# S7_RF.net
KiCad netlist of a schematic drawn in Altium Designer
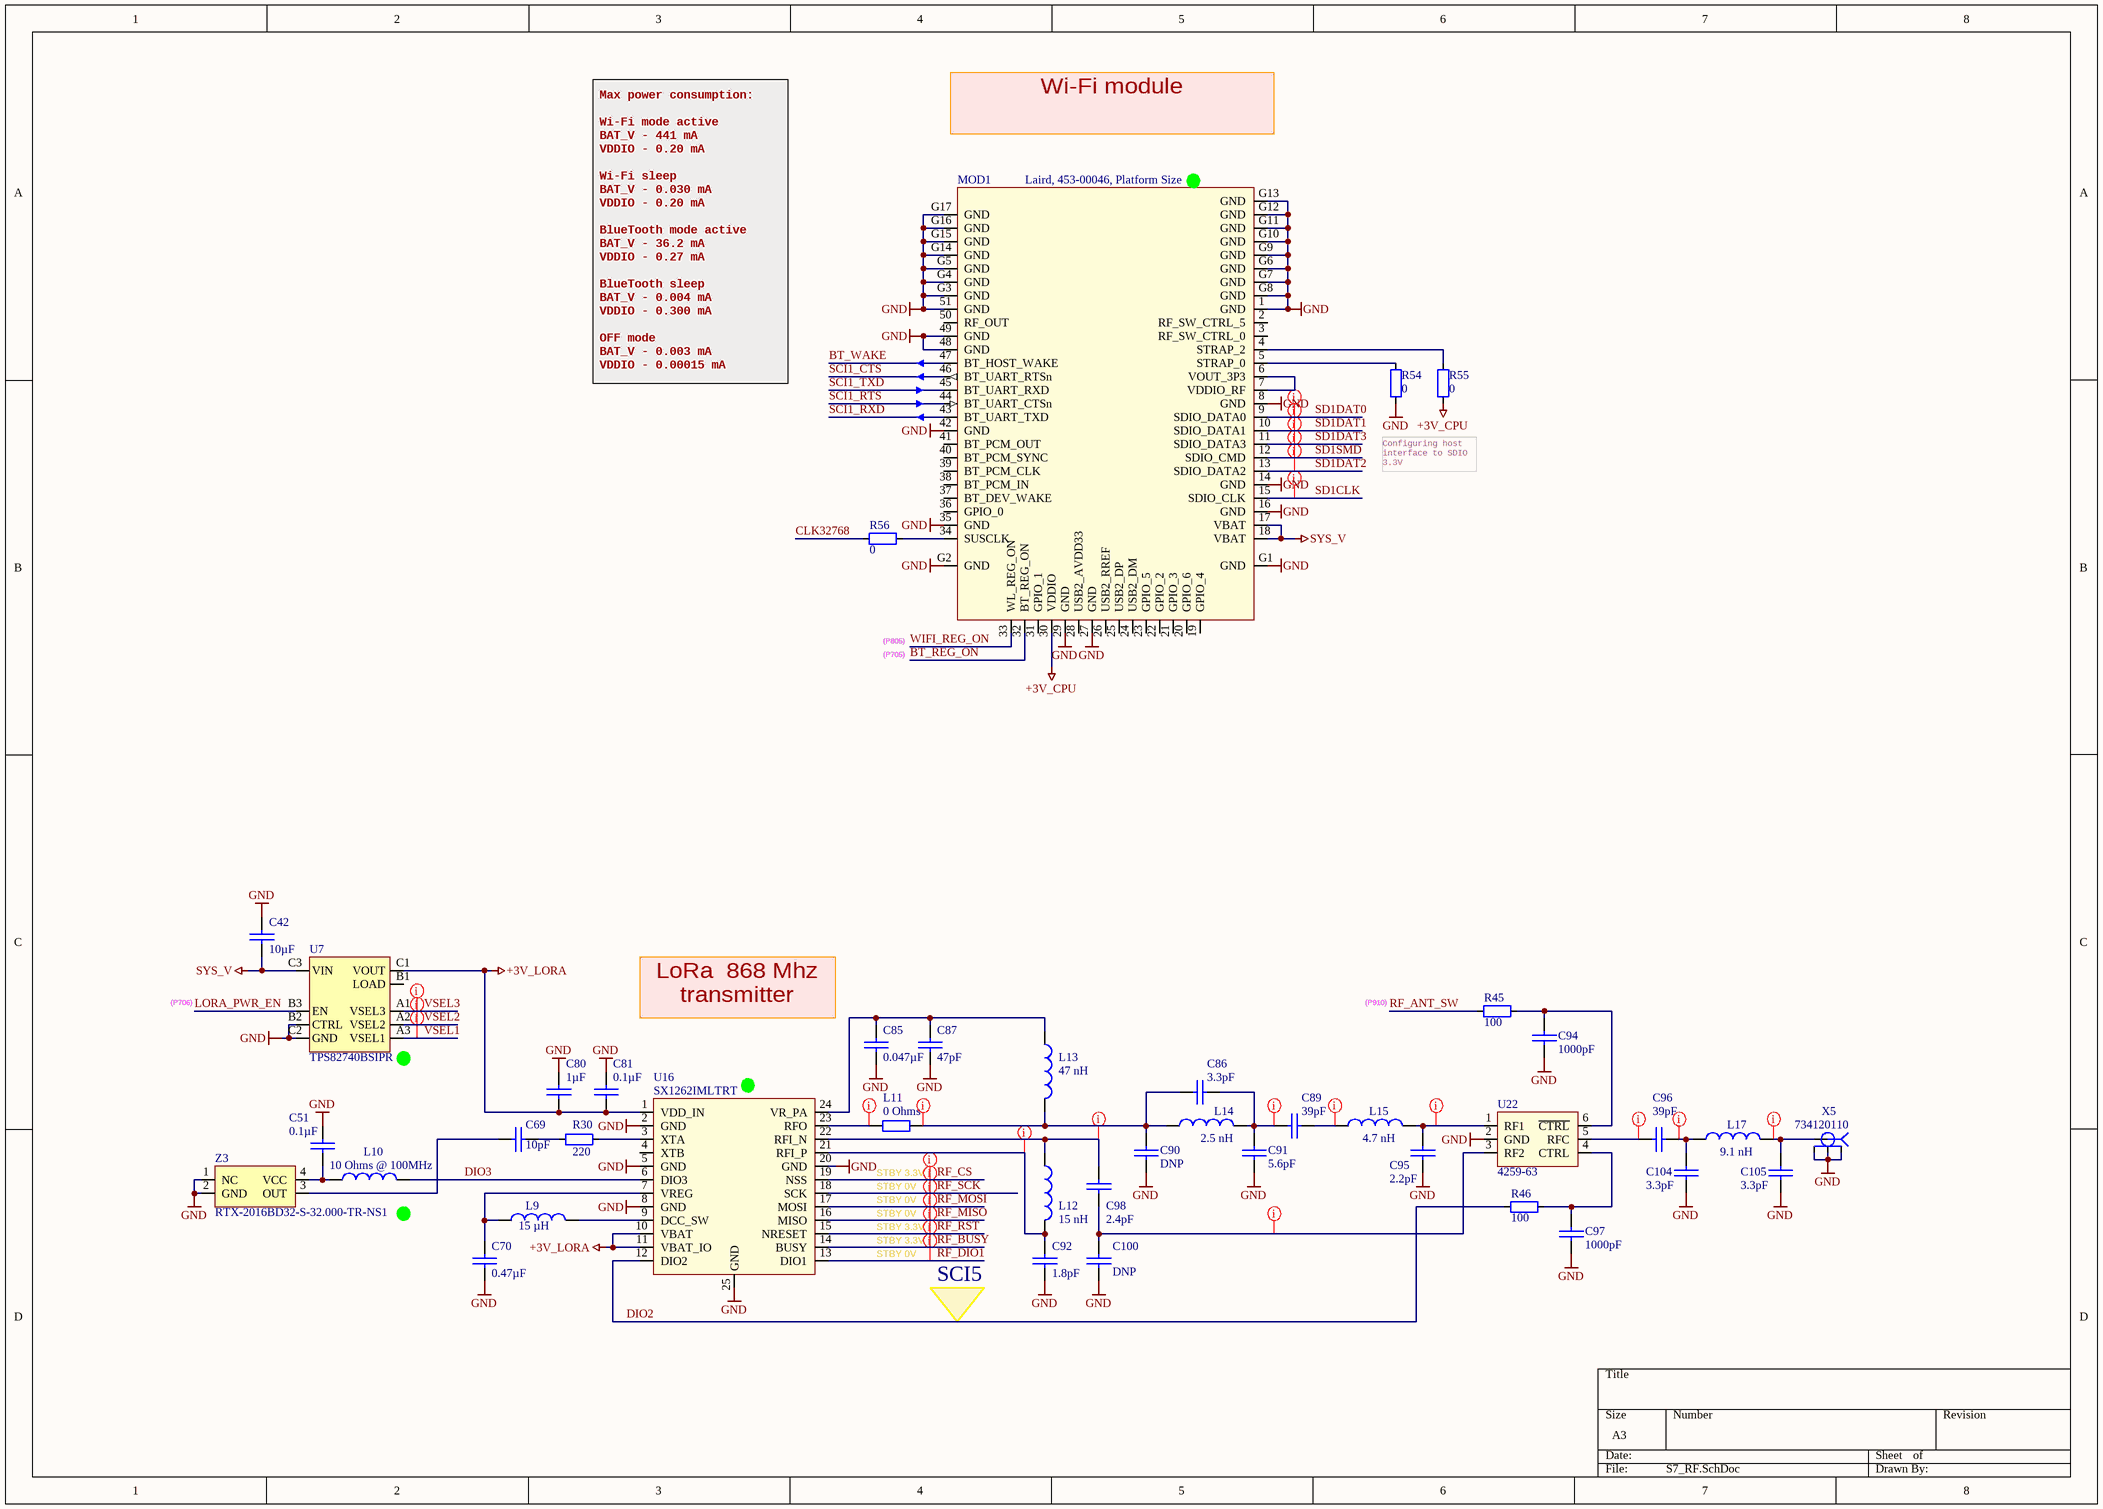
[diagram p0: S7_RF.SchDoc]

(export (version "E")
  (design (tool "Eeschema 10.0.6"))
  (components
    (comp (ref "C42")
      (value "10µF")
      (footprint "0603 CAP")
      (description "10µF, ±10%, 16V, X5R, 0603 (1608 Metric), -55°C ~ 85°C, -, Automotive")
      (fields
        (field (name "PART NUMBER") "GRT188R61C106KE13D")
        (field (name "MANUFACTURER") "Murata Electronics North America")
      )
      (libsource (lib "ea_PassivComps") (part "Capacitor"))
    )
    (comp (ref "C51")
      (value "0.1µF")
      (footprint "0402 CAP")
      (description "0.1µF, ±10%, 50V, X7R, 0402 (1005 Metric), -55°C ~ 125°C, -, General Purpose")
      (fields
        (field (name "PART NUMBER") "0402B104K500CT")
        (field (name "MANUFACTURER") "Walsin Technology Corporation")
      )
      (libsource (lib "ea_PassivComps") (part "Capacitor"))
    )
    (comp (ref "C69")
      (value "10pF")
      (footprint "0402 CAP")
      (fields
        (field (name "PART NUMBER") "GJM1555C1H100FB01D")
        (field (name "MANUFACTURER") "Murata Electronics North America")
        (field (name "PARTNUM") "490-11189-1-ND")
      )
      (libsource (lib "ea_PassivComps") (part "Capacitor"))
    )
    (comp (ref "C70")
      (value "0.47µF")
      (footprint "0402 CAP")
      (description "0.47µF, ±20%, 25V, X5R, 0402 (1005 Metric), -55°C ~ 85°C, -, Automotive")
      (fields
        (field (name "PART NUMBER") "GRT155R61E474ME01D")
        (field (name "MANUFACTURER") "Murata Electronics North America")
      )
      (libsource (lib "ea_PassivComps") (part "Capacitor"))
    )
    (comp (ref "C80")
      (value "1µF")
      (footprint "0402 CAP")
      (description "1µF, ±20%, 25V, X5R, 0402 (1005 Metric), -55°C ~ 85°C, -, General Purpose")
      (fields (field (name "PART NUMBER") "TMK105BJ105MV-F") (field (name "MANUFACTURER") "Taiyo Yuden"))
      (libsource (lib "ea_PassivComps") (part "Capacitor"))
    )
    (comp (ref "C81")
      (value "0.1µF")
      (footprint "0402 CAP")
      (description "0.1µF, ±10%, 50V, X7R, 0402 (1005 Metric), -55°C ~ 125°C, -, General Purpose")
      (fields
        (field (name "PART NUMBER") "0402B104K500CT")
        (field (name "MANUFACTURER") "Walsin Technology Corporation")
      )
      (libsource (lib "ea_PassivComps") (part "Capacitor"))
    )
    (comp (ref "C85")
      (value "0.047µF")
      (footprint "0402 CAP")
      (description "0.047µF, ±10%, 25V, X7R, 0402 (1005 Metric), -55°C ~ 125°C, -, General Purpose")
      (fields (field (name "PART NUMBER") "CC0402KRX7R8BB473") (field (name "MANUFACTURER") "Yageo"))
      (libsource (lib "ea_PassivComps") (part "Capacitor"))
    )
    (comp (ref "C86")
      (value "3.3pF")
      (footprint "0402 CAP")
      (description "3.3pF, ±0.1pF, 50V, C0G, NP0, 0402 (1005 Metric), -55°C ~ 125°C, -, RF, Microwave, High Frequency")
      (fields
        (field (name "PART NUMBER") "885392005011")
        (field (name "MANUFACTURER") "Wurth Electronics Inc.")
      )
      (libsource (lib "ea_PassivComps") (part "Capacitor"))
    )
    (comp (ref "C87")
      (value "47pF")
      (footprint "0402 CAP")
      (fields
        (field (name "PART NUMBER") "GJM1555C1H470FB01D")
        (field (name "MANUFACTURER") "Murata Electronics North America")
        (field (name "PARTNUM") "490-16376-1-ND")
      )
      (libsource (lib "ea_PassivComps") (part "Capacitor"))
    )
    (comp (ref "C89")
      (value "39pF")
      (footprint "0402 CAP")
      (fields
        (field (name "PART NUMBER") "GJM1555C1H390JB01D")
        (field (name "MANUFACTURER") "Murata Electronics North America")
        (field (name "PARTNUM") "490-17673-1-ND")
      )
      (libsource (lib "ea_PassivComps") (part "Capacitor"))
    )
    (comp (ref "C90")
      (value "DNP")
      (footprint "0402 CAP")
      (fields (field (name "Comment") "Capacitor_0402"))
      (libsource (lib "ea_Capacitors") (part "Capacitor_0402"))
    )
    (comp (ref "C91")
      (value "5.6pF")
      (footprint "0402 CAP")
      (fields
        (field (name "PART NUMBER") "GJM1555C1H5R6BB01D")
        (field (name "MANUFACTURER") "Murata Electronics North America")
        (field (name "PARTNUM") "490-11225-1-ND")
      )
      (libsource (lib "ea_PassivComps") (part "Capacitor"))
    )
    (comp (ref "C92")
      (value "1.8pF")
      (footprint "0402 CAP")
      (fields
        (field (name "PART NUMBER") "GJM1555C1H1R8BB01D")
        (field (name "MANUFACTURER") "Murata Electronics North America")
        (field (name "PARTNUM") "490-8089-1-ND")
      )
      (libsource (lib "ea_PassivComps") (part "Capacitor"))
    )
    (comp (ref "C94")
      (value "1000pF")
      (footprint "0402 CAP")
      (description "1000pF, ±5%, 50V, CH, 0402 (1005 Metric), -25°C ~ 85°C, Low ESL, General Purpose")
      (fields
        (field (name "PART NUMBER") "C1005CH1H102J050BA")
        (field (name "MANUFACTURER") "TDK Corporation")
      )
      (libsource (lib "ea_PassivComps") (part "Capacitor"))
    )
    (comp (ref "C95")
      (value "2.2pF")
      (footprint "0402 CAP")
      (fields
        (field (name "PART NUMBER") "CBR04C229B5GAC")
        (field (name "MANUFACTURER") "KEMET")
        (field (name "PARTNUM") "399-17527-1-ND")
      )
      (libsource (lib "ea_PassivComps") (part "Capacitor"))
    )
    (comp (ref "C96")
      (value "39pF")
      (footprint "0402 CAP")
      (fields
        (field (name "PART NUMBER") "GJM1555C1H390JB01D")
        (field (name "MANUFACTURER") "Murata Electronics North America")
        (field (name "PARTNUM") "490-17673-1-ND")
      )
      (libsource (lib "ea_PassivComps") (part "Capacitor"))
    )
    (comp (ref "C97")
      (value "1000pF")
      (footprint "0402 CAP")
      (description "1000pF, ±5%, 50V, CH, 0402 (1005 Metric), -25°C ~ 85°C, Low ESL, General Purpose")
      (fields
        (field (name "PART NUMBER") "C1005CH1H102J050BA")
        (field (name "MANUFACTURER") "TDK Corporation")
      )
      (libsource (lib "ea_PassivComps") (part "Capacitor"))
    )
    (comp (ref "C98")
      (value "2.4pF")
      (footprint "0402 CAP")
      (fields
        (field (name "PART NUMBER") "GJM1555C1H2R4BB01D")
        (field (name "MANUFACTURER") "Murata Electronics North America")
        (field (name "PARTNUM") "490-8093-1-ND")
      )
      (libsource (lib "ea_PassivComps") (part "Capacitor"))
    )
    (comp (ref "C100")
      (value "DNP")
      (footprint "0402 CAP")
      (fields (field (name "Comment") "Capacitor_0402"))
      (libsource (lib "ea_Capacitors") (part "Capacitor_0402"))
    )
    (comp (ref "C104")
      (value "3.3pF")
      (footprint "0402 CAP")
      (description "3.3pF, ±0.1pF, 50V, C0G, NP0, 0402 (1005 Metric), -55°C ~ 125°C, -, RF, Microwave, High Frequency")
      (fields
        (field (name "PART NUMBER") "885392005011")
        (field (name "MANUFACTURER") "Wurth Electronics Inc.")
      )
      (libsource (lib "ea_PassivComps") (part "Capacitor"))
    )
    (comp (ref "C105")
      (value "3.3pF")
      (footprint "0402 CAP")
      (description "3.3pF, ±0.1pF, 50V, C0G, NP0, 0402 (1005 Metric), -55°C ~ 125°C, -, RF, Microwave, High Frequency")
      (fields
        (field (name "PART NUMBER") "885392005011")
        (field (name "MANUFACTURER") "Wurth Electronics Inc.")
      )
      (libsource (lib "ea_PassivComps") (part "Capacitor"))
    )
    (comp (ref "L9")
      (value "15 µH")
      (footprint "2012[0805]")
      (description "15µH Shielded Multilayer Inductor 250mA 950 mOhm 0805 (2012 Metric)")
      (fields (field (name "MANUFACTURER") "TDK Corporation") (field (name "PARTNUM") "445-6397-1-ND"))
      (libsource (lib "ea_RF_inductors") (part "MLZ2012M150WT000"))
    )
    (comp (ref "L10")
      (value "10 Ohms @ 100MHz")
      (footprint "INDC1005-0402")
      (description "10 Ohms @ 100MHz 1 Power Line Ferrite Bead 0402 (1005 Metric) 1A 25 mOhm")
      (fields
        (field (name "MANUFACTURER") "Murata Electronics North America")
        (field (name "PARTNUM") "490-5976-1-ND")
      )
      (libsource (lib "ea_RF_inductors") (part "BLM15PG100SN1D"))
    )
    (comp (ref "L11")
      (value "0 Ohms")
      (footprint "INDC1005-0402")
      (description "0 Ohms Jumper 0.063W, 1/16W Chip Resistor 0402 (1005 Metric) Automotive AEC-Q200 Thick Film")
      (fields (field (name "MANUFACTURER") "Vishay Dale") (field (name "PARTNUM") "541-0.0JCT-ND"))
      (libsource (lib "ea_RF_inductors") (part "CRCW04020000Z0ED"))
    )
    (comp (ref "L12")
      (value "15 nH")
      (footprint "INDC1005-0402")
      (description "15nH Unshielded Wirewound Inductor 460mA 160 mOhm Max 0402 (1006 Metric)")
      (fields (field (name "MANUFACTURER") "Murata") (field (name "TOLERANCE") "±3%"))
      (libsource (lib "ea_RF_inductors") (part "LQW15AN15NH00D"))
    )
    (comp (ref "L13")
      (value "47 nH")
      (footprint "INDC1005-0402")
      (description "47nH Unshielded Wirewound Inductor 210mA 1.08 Ohm Max 0402 (1005 Metric)")
      (fields (field (name "MANUFACTURER") "Murata") (field (name "TOLERANCE") "±5%"))
      (libsource (lib "ea_RF_inductors") (part "LQW15AN47NJ00D"))
    )
    (comp (ref "L14")
      (value "2.5 nH")
      (footprint "INDC1005-0402")
      (description "2.5nH Unshielded Wirewound Inductor 850mA 50 mOhm Max 0402 (1006 Metric)")
      (fields (field (name "MANUFACTURER") "Murata") (field (name "TOLERANCE") "±0.2nH"))
      (libsource (lib "ea_RF_inductors") (part "LQW15AN2N5C00D"))
    )
    (comp (ref "L15")
      (value "4.7 nH")
      (footprint "INDC1005-0402")
      (description "4.7nH Unshielded Wirewound Inductor 750mA 70 mOhm Max 0402 (1006 Metric)")
      (fields
        (field (name "MANUFACTURER") "Murata Electronics North America")
        (field (name "TOLERANCE") "±0.2nH")
      )
      (libsource (lib "ea_RF_inductors") (part "LQW15AN4N7C00D"))
    )
    (comp (ref "L17")
      (value "9.1 nH")
      (footprint "INDC1005-0402")
      (description "9.1nH Unshielded Wirewound Inductor 540mA 140 mOhm Max 0402 (1006 Metric)")
      (fields
        (field (name "MANUFACTURER") "Murata Electronics North America")
        (field (name "TOLERANCE") "±3%")
      )
      (libsource (lib "ea_RF_inductors") (part "LQW15AN9N1H00D"))
    )
    (comp (ref "MOD1")
      (value "Laird, 453-00046, Platform Size")
      (footprint "LWB5+ 453-00045C")
      (description "Module, Sterling LWB5+")
      (fields (field (name "MANUFACTURER") "Laird"))
      (libsource (lib "ea_WiFi_modules") (part "CMP-MOD-453-00012-1.4"))
    )
    (comp (ref "R30")
      (value "220")
      (footprint "0402")
      (fields
        (field (name "MANUFACTURER") "Yageo")
        (field (name "TOLERANCE") "±1%")
        (field (name "VOLTAGE") "75V")
      )
      (libsource (lib "") (part "Resistor_1"))
    )
    (comp (ref "R45")
      (value "100")
      (footprint "0402")
      (fields
        (field (name "MANUFACTURER") "Stackpole Electronics Inc")
        (field (name "TOLERANCE") "±1%")
        (field (name "VOLTAGE") "75V")
      )
      (libsource (lib "ea_PassivComps") (part "Resistor"))
    )
    (comp (ref "R46")
      (value "100")
      (footprint "0402")
      (fields
        (field (name "MANUFACTURER") "Stackpole Electronics Inc")
        (field (name "TOLERANCE") "±1%")
        (field (name "VOLTAGE") "75V")
      )
      (libsource (lib "ea_PassivComps") (part "Resistor"))
    )
    (comp (ref "R54")
      (value "0")
      (footprint "0402")
      (description "0 Ohm, Thick Film, -55..+155, 0402")
      (fields (field (name "MANUFACTURER") "Rohm Semiconductor") (field (name "VOLTAGE") "50 V"))
      (libsource (lib "ea_Resistors_0402") (part "MCR01MZPJ000"))
    )
    (comp (ref "R55")
      (value "0")
      (footprint "0402")
      (description "0 Ohm, Thick Film, -55..+155, 0402")
      (fields (field (name "MANUFACTURER") "Rohm Semiconductor") (field (name "VOLTAGE") "50 V"))
      (libsource (lib "ea_Resistors_0402") (part "MCR01MZPJ000"))
    )
    (comp (ref "R56")
      (value "0")
      (footprint "0402")
      (description "0 Ohm, Thick Film, -55..+155, 0402")
      (fields (field (name "MANUFACTURER") "Rohm Semiconductor") (field (name "VOLTAGE") "50 V"))
      (libsource (lib "") (part "MCR01MZPJ000_1"))
    )
    (comp (ref "U7")
      (value "TPS82740BSIPR")
      (footprint "MicroSiP")
      (fields (field (name "MANUFACTURER") "Texas Instruments") (field (name "PARTNUM") "296-46481-1-ND"))
      (libsource (lib "ea_IC_Power_Reg_Ref_Sw") (part "TPS82740BSIPR"))
    )
    (comp (ref "U16")
      (value "SX1262IMLTRT")
      (footprint "VQFN24")
      (description "IC RF TxRx Only General ISM < 1GHz LoRaWAN 150MHz ~ 960MHz 24-VFQFN Exposed Pad")
      (fields (field (name "MANUFACTURER") "Semtech Corporation"))
      (libsource (lib "ea_IC_RF") (part "SX1262IMLTRT"))
    )
    (comp (ref "U22")
      (value "4259-63")
      (footprint "SC70-6")
      (description "PE4259  RF Switch IC General Purpose SPDT 3GHz 50 Ohm SC-70-6")
      (fields
        (field (name "MANUFACTURER") "pSemi")
        (field (name "PARTNUM") "1046-1011-2-ND")
        (field (name "PARTNAME") "4259-63")
      )
      (libsource (lib "ea_IC_RF") (part "4259-63"))
    )
    (comp (ref "X5")
      (value "734120110")
      (footprint "0734120110")
      (description "U.FL (UMCC) Connector Receptacle, Male Pin 50 Ohm Surface Mount Solder")
      (fields (field (name "MANUFACTURER") "Molex") (field (name "PARTNUM") "WM5587TR-ND"))
      (libsource (lib "ea_Connectors_RF") (part "0734120110"))
    )
    (comp (ref "Z3")
      (value "RTX-2016BD32-S-32.000-TR-NS1")
      (footprint "4-SMD 2.00mm x 1.60mm")
      (description "32MHz TCXO Clipped Sine Wave Oscillator 2.8V, ±1ppm,  4-SMD, No Lead,  \r\n-40°C ~ 85°C")
      (fields
        (field (name "MANUFACTURER") "Raltron Electronics")
        (field (name "PARTNUM") "2151-RTX-2016BD32-S-52.000-TR-NS1CT-ND")
      )
      (libsource (lib "ea_OSC_CLK_GEN") (part "RTX-2016BD32-S-52.000-TR-NS1"))
    )
  )
  (nets
    (net (code "1") (name "+3V_CPU") (class "Default")
      (node (ref "MOD1") (pin "30") (pinfunction "VDDIO_30") (pintype "passive"))
      (node (ref "R55") (pin "1") (pinfunction "1_1") (pintype "passive"))
    )
    (net (code "2") (name "+3V_LORA") (class "Default")
      (node (ref "C80") (pin "2") (pinfunction "2_2") (pintype "passive"))
      (node (ref "C81") (pin "2") (pinfunction "2_2") (pintype "passive"))
      (node (ref "U16") (pin "1") (pinfunction "VDD_IN_1") (pintype "power_in"))
      (node (ref "U16") (pin "10") (pinfunction "VBAT_10") (pintype "power_in"))
      (node (ref "U16") (pin "11") (pinfunction "VBAT_IO_11") (pintype "power_in"))
      (node (ref "U7") (pin "C1") (pinfunction "VOUT_C1") (pintype "passive"))
    )
    (net (code "3") (name "/BT_REG_ON") (class "Default")
      (node (ref "MOD1") (pin "32") (pinfunction "BT_REG_ON_32") (pintype "passive"))
    )
    (net (code "4") (name "/BT_WAKE") (class "Default")
      (node (ref "MOD1") (pin "47") (pinfunction "BT_HOST_WAKE_47") (pintype "passive"))
    )
    (net (code "5") (name "/CLK32768") (class "Default")
      (node (ref "R56") (pin "2") (pinfunction "2_2") (pintype "passive"))
    )
    (net (code "6") (name "/DIO2") (class "Default")
      (node (ref "R46") (pin "2") (pinfunction "2_2") (pintype "passive"))
      (node (ref "U16") (pin "12") (pinfunction "DIO2_12") (pintype "passive"))
    )
    (net (code "7") (name "/DIO3") (class "Default")
      (node (ref "L10") (pin "2") (pinfunction "2_2") (pintype "passive"))
      (node (ref "U16") (pin "6") (pinfunction "DIO3_6") (pintype "passive"))
    )
    (net (code "8") (name "/LORA_PWR_EN") (class "Default")
      (node (ref "U7") (pin "B3") (pinfunction "EN_B3") (pintype "passive"))
    )
    (net (code "9") (name "/RF_ANT_SW") (class "Default")
      (node (ref "R45") (pin "2") (pinfunction "2_2") (pintype "passive"))
    )
    (net (code "10") (name "/RF_BUSY") (class "Default")
      (node (ref "U16") (pin "14") (pinfunction "BUSY_14") (pintype "passive"))
    )
    (net (code "11") (name "/RF_CS") (class "Default")
      (node (ref "U16") (pin "19") (pinfunction "NSS_19") (pintype "passive"))
    )
    (net (code "12") (name "/RF_DIO1") (class "Default")
      (node (ref "U16") (pin "13") (pinfunction "DIO1_13") (pintype "passive"))
    )
    (net (code "13") (name "/RF_MISO") (class "Default")
      (node (ref "U16") (pin "16") (pinfunction "MISO_16") (pintype "passive"))
    )
    (net (code "14") (name "/RF_MOSI") (class "Default")
      (node (ref "U16") (pin "17") (pinfunction "MOSI_17") (pintype "passive"))
    )
    (net (code "15") (name "/RF_RST") (class "Default")
      (node (ref "U16") (pin "15") (pinfunction "NRESET_15") (pintype "passive"))
    )
    (net (code "16") (name "/RF_SCK") (class "Default")
      (node (ref "U16") (pin "18") (pinfunction "SCK_18") (pintype "passive"))
    )
    (net (code "17") (name "/SCI1_CTS") (class "Default")
      (node (ref "MOD1") (pin "46") (pinfunction "BT_UART_RTSn_46") (pintype "output"))
    )
    (net (code "18") (name "/SCI1_RTS") (class "Default")
      (node (ref "MOD1") (pin "44") (pinfunction "BT_UART_CTSn_44") (pintype "input"))
    )
    (net (code "19") (name "/SCI1_RXD") (class "Default")
      (node (ref "MOD1") (pin "43") (pinfunction "BT_UART_TXD_43") (pintype "passive"))
    )
    (net (code "20") (name "/SCI1_TXD") (class "Default")
      (node (ref "MOD1") (pin "45") (pinfunction "BT_UART_RXD_45") (pintype "passive"))
    )
    (net (code "21") (name "/SD1CLK") (class "Default")
      (node (ref "MOD1") (pin "15") (pinfunction "SDIO_CLK_15") (pintype "passive"))
    )
    (net (code "22") (name "/SD1DAT0") (class "Default")
      (node (ref "MOD1") (pin "9") (pinfunction "SDIO_DATA0_9") (pintype "passive"))
    )
    (net (code "23") (name "/SD1DAT1") (class "Default")
      (node (ref "MOD1") (pin "10") (pinfunction "SDIO_DATA1_10") (pintype "passive"))
    )
    (net (code "24") (name "/SD1DAT2") (class "Default")
      (node (ref "MOD1") (pin "13") (pinfunction "SDIO_DATA2_13") (pintype "passive"))
    )
    (net (code "25") (name "/SD1DAT3") (class "Default")
      (node (ref "MOD1") (pin "11") (pinfunction "SDIO_DATA3_11") (pintype "passive"))
    )
    (net (code "26") (name "/SD1SMD") (class "Default")
      (node (ref "MOD1") (pin "12") (pinfunction "SDIO_CMD_12") (pintype "passive"))
    )
    (net (code "27") (name "/VSEL1") (class "Default")
      (node (ref "U7") (pin "A3") (pinfunction "VSEL1_A3") (pintype "passive"))
    )
    (net (code "28") (name "/VSEL2") (class "Default")
      (node (ref "U7") (pin "A2") (pinfunction "VSEL2_A2") (pintype "passive"))
    )
    (net (code "29") (name "/VSEL3") (class "Default")
      (node (ref "U7") (pin "A1") (pinfunction "VSEL3_A1") (pintype "passive"))
    )
    (net (code "30") (name "/WIFI_REG_ON") (class "Default")
      (node (ref "MOD1") (pin "33") (pinfunction "WL_REG_ON_33") (pintype "passive"))
    )
    (net (code "31") (name "GND") (class "Default")
      (node (ref "C100") (pin "2") (pinfunction "2_2") (pintype "passive"))
      (node (ref "C104") (pin "1") (pinfunction "1_1") (pintype "passive"))
      (node (ref "C105") (pin "1") (pinfunction "1_1") (pintype "passive"))
      (node (ref "C42") (pin "1") (pinfunction "1_1") (pintype "passive"))
      (node (ref "C51") (pin "1") (pinfunction "1_1") (pintype "passive"))
      (node (ref "C70") (pin "2") (pinfunction "2_2") (pintype "passive"))
      (node (ref "C80") (pin "1") (pinfunction "1_1") (pintype "passive"))
      (node (ref "C81") (pin "1") (pinfunction "1_1") (pintype "passive"))
      (node (ref "C85") (pin "2") (pinfunction "2_2") (pintype "passive"))
      (node (ref "C87") (pin "2") (pinfunction "2_2") (pintype "passive"))
      (node (ref "C90") (pin "2") (pinfunction "2_2") (pintype "passive"))
      (node (ref "C91") (pin "2") (pinfunction "2_2") (pintype "passive"))
      (node (ref "C92") (pin "2") (pinfunction "2_2") (pintype "passive"))
      (node (ref "C94") (pin "1") (pinfunction "1_1") (pintype "passive"))
      (node (ref "C95") (pin "2") (pinfunction "2_2") (pintype "passive"))
      (node (ref "C97") (pin "1") (pinfunction "1_1") (pintype "passive"))
      (node (ref "MOD1") (pin "1") (pinfunction "GND_1") (pintype "passive"))
      (node (ref "MOD1") (pin "14") (pinfunction "GND_14") (pintype "passive"))
      (node (ref "MOD1") (pin "16") (pinfunction "GND_16") (pintype "passive"))
      (node (ref "MOD1") (pin "27") (pinfunction "GND_27") (pintype "passive"))
      (node (ref "MOD1") (pin "29") (pinfunction "GND_29") (pintype "passive"))
      (node (ref "MOD1") (pin "35") (pinfunction "GND_35") (pintype "passive"))
      (node (ref "MOD1") (pin "42") (pinfunction "GND_42") (pintype "passive"))
      (node (ref "MOD1") (pin "48") (pinfunction "GND_48") (pintype "passive"))
      (node (ref "MOD1") (pin "49") (pinfunction "GND_49") (pintype "passive"))
      (node (ref "MOD1") (pin "51") (pinfunction "GND_51") (pintype "passive"))
      (node (ref "MOD1") (pin "8") (pinfunction "GND_8") (pintype "passive"))
      (node (ref "MOD1") (pin "G1") (pinfunction "GND_G1") (pintype "passive"))
      (node (ref "MOD1") (pin "G10") (pinfunction "GND_G10") (pintype "passive"))
      (node (ref "MOD1") (pin "G11") (pinfunction "GND_G11") (pintype "passive"))
      (node (ref "MOD1") (pin "G12") (pinfunction "GND_G12") (pintype "passive"))
      (node (ref "MOD1") (pin "G13") (pinfunction "GND_G13") (pintype "passive"))
      (node (ref "MOD1") (pin "G14") (pinfunction "GND_G14") (pintype "passive"))
      (node (ref "MOD1") (pin "G15") (pinfunction "GND_G15") (pintype "passive"))
      (node (ref "MOD1") (pin "G16") (pinfunction "GND_G16") (pintype "passive"))
      (node (ref "MOD1") (pin "G17") (pinfunction "GND_G17") (pintype "passive"))
      (node (ref "MOD1") (pin "G2") (pinfunction "GND_G2") (pintype "passive"))
      (node (ref "MOD1") (pin "G3") (pinfunction "GND_G3") (pintype "passive"))
      (node (ref "MOD1") (pin "G4") (pinfunction "GND_G4") (pintype "passive"))
      (node (ref "MOD1") (pin "G5") (pinfunction "GND_G5") (pintype "passive"))
      (node (ref "MOD1") (pin "G6") (pinfunction "GND_G6") (pintype "passive"))
      (node (ref "MOD1") (pin "G7") (pinfunction "GND_G7") (pintype "passive"))
      (node (ref "MOD1") (pin "G8") (pinfunction "GND_G8") (pintype "passive"))
      (node (ref "MOD1") (pin "G9") (pinfunction "GND_G9") (pintype "passive"))
      (node (ref "R54") (pin "1") (pinfunction "1_1") (pintype "passive"))
      (node (ref "U16") (pin "2") (pinfunction "GND_2") (pintype "passive"))
      (node (ref "U16") (pin "20") (pinfunction "GND_20") (pintype "passive"))
      (node (ref "U16") (pin "25") (pinfunction "GND_25") (pintype "passive"))
      (node (ref "U16") (pin "5") (pinfunction "GND_5") (pintype "passive"))
      (node (ref "U16") (pin "8") (pinfunction "GND_8") (pintype "passive"))
      (node (ref "U22") (pin "2") (pinfunction "GND_2") (pintype "passive"))
      (node (ref "U7") (pin "B2") (pinfunction "CTRL_B2") (pintype "passive"))
      (node (ref "U7") (pin "C2") (pinfunction "GND_C2") (pintype "passive"))
      (node (ref "X5") (pin "2") (pinfunction "2_2") (pintype "passive"))
      (node (ref "X5") (pin "3") (pinfunction "3_3") (pintype "passive"))
      (node (ref "X5") (pin "4") (pinfunction "3_4") (pintype "passive"))
      (node (ref "Z3") (pin "1") (pinfunction "NC_1") (pintype "passive"))
      (node (ref "Z3") (pin "2") (pinfunction "GND_2") (pintype "passive"))
    )
    (net (code "32") (name "Net-(C69-Pad2)") (class "Default")
      (node (ref "C69") (pin "2") (pinfunction "2_2") (pintype "passive"))
      (node (ref "R30") (pin "1") (pinfunction "1_1") (pintype "passive"))
    )
    (net (code "33") (name "Net-(C86-Pad1)") (class "Default")
      (node (ref "C86") (pin "1") (pinfunction "1_1") (pintype "passive"))
      (node (ref "C90") (pin "1") (pinfunction "1_1") (pintype "passive"))
      (node (ref "L11") (pin "2") (pinfunction "2_2") (pintype "passive"))
      (node (ref "L13") (pin "2") (pinfunction "2_2") (pintype "passive"))
      (node (ref "L14") (pin "1") (pinfunction "1_1") (pintype "passive"))
    )
    (net (code "34") (name "Net-(C86-Pad2)") (class "Default")
      (node (ref "C86") (pin "2") (pinfunction "2_2") (pintype "passive"))
      (node (ref "C89") (pin "1") (pinfunction "1_1") (pintype "passive"))
      (node (ref "C91") (pin "1") (pinfunction "1_1") (pintype "passive"))
      (node (ref "L14") (pin "2") (pinfunction "2_2") (pintype "passive"))
    )
    (net (code "35") (name "Net-(C89-Pad2)") (class "Default")
      (node (ref "C89") (pin "2") (pinfunction "2_2") (pintype "passive"))
      (node (ref "L15") (pin "1") (pinfunction "1_1") (pintype "passive"))
    )
    (net (code "36") (name "Net-(C104-Pad2)") (class "Default")
      (node (ref "C104") (pin "2") (pinfunction "2_2") (pintype "passive"))
      (node (ref "C96") (pin "2") (pinfunction "2_2") (pintype "passive"))
      (node (ref "L17") (pin "1") (pinfunction "1_1") (pintype "passive"))
    )
    (net (code "37") (name "Net-(MOD1-STRAP_0)") (class "Default")
      (node (ref "MOD1") (pin "5") (pinfunction "STRAP_0_5") (pintype "passive"))
      (node (ref "R54") (pin "2") (pinfunction "2_2") (pintype "passive"))
    )
    (net (code "38") (name "Net-(MOD1-STRAP_2)") (class "Default")
      (node (ref "MOD1") (pin "4") (pinfunction "STRAP_2_4") (pintype "passive"))
      (node (ref "R55") (pin "2") (pinfunction "2_2") (pintype "passive"))
    )
    (net (code "39") (name "Net-(MOD1-SUSCLK)") (class "Default")
      (node (ref "MOD1") (pin "34") (pinfunction "SUSCLK_34") (pintype "passive"))
      (node (ref "R56") (pin "1") (pinfunction "1_1") (pintype "passive"))
    )
    (net (code "40") (name "Net-(MOD1-VDDIO_RF)") (class "Default")
      (node (ref "MOD1") (pin "6") (pinfunction "VOUT_3P3_6") (pintype "passive"))
      (node (ref "MOD1") (pin "7") (pinfunction "VDDIO_RF_7") (pintype "passive"))
    )
    (net (code "41") (name "Net-(U16-DCC_SW)") (class "Default")
      (node (ref "L9") (pin "2") (pinfunction "2_2") (pintype "passive"))
      (node (ref "U16") (pin "9") (pinfunction "DCC_SW_9") (pintype "power_in"))
    )
    (net (code "42") (name "Net-(U16-RFI_N)") (class "Default")
      (node (ref "C98") (pin "1") (pinfunction "1_1") (pintype "passive"))
      (node (ref "L12") (pin "1") (pinfunction "1_1") (pintype "passive"))
      (node (ref "U16") (pin "22") (pinfunction "RFI_N_22") (pintype "passive"))
    )
    (net (code "43") (name "Net-(U16-RFI_P)") (class "Default")
      (node (ref "C92") (pin "1") (pinfunction "1_1") (pintype "passive"))
      (node (ref "L12") (pin "2") (pinfunction "2_2") (pintype "passive"))
      (node (ref "U16") (pin "21") (pinfunction "RFI_P_21") (pintype "passive"))
    )
    (net (code "44") (name "Net-(U16-RFO)") (class "Default")
      (node (ref "L11") (pin "1") (pinfunction "1_1") (pintype "passive"))
      (node (ref "U16") (pin "23") (pinfunction "RFO_23") (pintype "passive"))
    )
    (net (code "45") (name "Net-(U16-VREG)") (class "Default")
      (node (ref "C70") (pin "1") (pinfunction "1_1") (pintype "passive"))
      (node (ref "L9") (pin "1") (pinfunction "1_1") (pintype "passive"))
      (node (ref "U16") (pin "7") (pinfunction "VREG_7") (pintype "power_in"))
    )
    (net (code "46") (name "Net-(U16-VR_PA)") (class "Default")
      (node (ref "C85") (pin "1") (pinfunction "1_1") (pintype "passive"))
      (node (ref "C87") (pin "1") (pinfunction "1_1") (pintype "passive"))
      (node (ref "L13") (pin "1") (pinfunction "1_1") (pintype "passive"))
      (node (ref "U16") (pin "24") (pinfunction "VR_PA_24") (pintype "power_in"))
    )
    (net (code "47") (name "Net-(U16-XTA)") (class "Default")
      (node (ref "R30") (pin "2") (pinfunction "2_2") (pintype "passive"))
      (node (ref "U16") (pin "3") (pinfunction "XTA_3") (pintype "passive"))
    )
    (net (code "48") (name "Net-(U22-CTRL)") (class "Default")
      (node (ref "C97") (pin "2") (pinfunction "2_2") (pintype "passive"))
      (node (ref "R46") (pin "1") (pinfunction "1_1") (pintype "passive"))
      (node (ref "U22") (pin "4") (pinfunction "CTRL_4") (pintype "passive"))
    )
    (net (code "49") (name "Net-(U22-RF1)") (class "Default")
      (node (ref "C95") (pin "1") (pinfunction "1_1") (pintype "passive"))
      (node (ref "L15") (pin "2") (pinfunction "2_2") (pintype "passive"))
      (node (ref "U22") (pin "1") (pinfunction "RF1_1") (pintype "passive"))
    )
    (net (code "50") (name "Net-(U22-RF2)") (class "Default")
      (node (ref "C100") (pin "1") (pinfunction "1_1") (pintype "passive"))
      (node (ref "C98") (pin "2") (pinfunction "2_2") (pintype "passive"))
      (node (ref "U22") (pin "3") (pinfunction "RF2_3") (pintype "passive"))
    )
    (net (code "51") (name "Net-(U22-RFC)") (class "Default")
      (node (ref "C96") (pin "1") (pinfunction "1_1") (pintype "passive"))
      (node (ref "U22") (pin "5") (pinfunction "RFC_5") (pintype "passive"))
    )
    (net (code "52") (name "Net-(U22-~{CTRL})") (class "Default")
      (node (ref "C94") (pin "2") (pinfunction "2_2") (pintype "passive"))
      (node (ref "R45") (pin "1") (pinfunction "1_1") (pintype "passive"))
      (node (ref "U22") (pin "6") (pinfunction "~{CTRL}_6") (pintype "passive"))
    )
    (net (code "53") (name "Net-(X5-Sig)") (class "Default")
      (node (ref "C105") (pin "2") (pinfunction "2_2") (pintype "passive"))
      (node (ref "L17") (pin "2") (pinfunction "2_2") (pintype "passive"))
      (node (ref "X5") (pin "1") (pinfunction "Sig_1") (pintype "passive"))
    )
    (net (code "54") (name "Net-(Z3-OUT)") (class "Default")
      (node (ref "C69") (pin "1") (pinfunction "1_1") (pintype "passive"))
      (node (ref "Z3") (pin "3") (pinfunction "OUT_3") (pintype "passive"))
    )
    (net (code "55") (name "Net-(Z3-VCC)") (class "Default")
      (node (ref "C51") (pin "2") (pinfunction "2_2") (pintype "passive"))
      (node (ref "L10") (pin "1") (pinfunction "1_1") (pintype "passive"))
      (node (ref "Z3") (pin "4") (pinfunction "VCC_4") (pintype "passive"))
    )
    (net (code "56") (name "SYS_V") (class "Default")
      (node (ref "C42") (pin "2") (pinfunction "2_2") (pintype "passive"))
      (node (ref "MOD1") (pin "17") (pinfunction "VBAT_17") (pintype "passive"))
      (node (ref "MOD1") (pin "18") (pinfunction "VBAT_18") (pintype "passive"))
      (node (ref "U7") (pin "C3") (pinfunction "VIN_C3") (pintype "passive"))
    )
    (net (code "57") (name "unconnected-(MOD1-BT_DEV_WAKE-Pad37)") (class "Default")
      (node (ref "MOD1") (pin "37") (pinfunction "BT_DEV_WAKE_37") (pintype "passive"))
    )
    (net (code "58") (name "unconnected-(MOD1-BT_PCM_CLK-Pad39)") (class "Default")
      (node (ref "MOD1") (pin "39") (pinfunction "BT_PCM_CLK_39") (pintype "passive"))
    )
    (net (code "59") (name "unconnected-(MOD1-BT_PCM_IN-Pad38)") (class "Default")
      (node (ref "MOD1") (pin "38") (pinfunction "BT_PCM_IN_38") (pintype "passive"))
    )
    (net (code "60") (name "unconnected-(MOD1-BT_PCM_OUT-Pad41)") (class "Default")
      (node (ref "MOD1") (pin "41") (pinfunction "BT_PCM_OUT_41") (pintype "passive"))
    )
    (net (code "61") (name "unconnected-(MOD1-BT_PCM_SYNC-Pad40)") (class "Default")
      (node (ref "MOD1") (pin "40") (pinfunction "BT_PCM_SYNC_40") (pintype "passive"))
    )
    (net (code "62") (name "unconnected-(MOD1-GPIO_0-Pad36)") (class "Default")
      (node (ref "MOD1") (pin "36") (pinfunction "GPIO_0_36") (pintype "passive"))
    )
    (net (code "63") (name "unconnected-(MOD1-GPIO_1-Pad31)") (class "Default")
      (node (ref "MOD1") (pin "31") (pinfunction "GPIO_1_31") (pintype "passive"))
    )
    (net (code "64") (name "unconnected-(MOD1-GPIO_2-Pad22)") (class "Default")
      (node (ref "MOD1") (pin "22") (pinfunction "GPIO_2_22") (pintype "passive"))
    )
    (net (code "65") (name "unconnected-(MOD1-GPIO_3-Pad21)") (class "Default")
      (node (ref "MOD1") (pin "21") (pinfunction "GPIO_3_21") (pintype "passive"))
    )
    (net (code "66") (name "unconnected-(MOD1-GPIO_4-Pad19)") (class "Default")
      (node (ref "MOD1") (pin "19") (pinfunction "GPIO_4_19") (pintype "passive"))
    )
    (net (code "67") (name "unconnected-(MOD1-GPIO_5-Pad23)") (class "Default")
      (node (ref "MOD1") (pin "23") (pinfunction "GPIO_5_23") (pintype "passive"))
    )
    (net (code "68") (name "unconnected-(MOD1-GPIO_6-Pad20)") (class "Default")
      (node (ref "MOD1") (pin "20") (pinfunction "GPIO_6_20") (pintype "passive"))
    )
    (net (code "69") (name "unconnected-(MOD1-RF_OUT-Pad50)") (class "Default")
      (node (ref "MOD1") (pin "50") (pinfunction "RF_OUT_50") (pintype "passive"))
    )
    (net (code "70") (name "unconnected-(MOD1-RF_SW_CTRL_0-Pad3)") (class "Default")
      (node (ref "MOD1") (pin "3") (pinfunction "RF_SW_CTRL_0_3") (pintype "passive"))
    )
    (net (code "71") (name "unconnected-(MOD1-RF_SW_CTRL_5-Pad2)") (class "Default")
      (node (ref "MOD1") (pin "2") (pinfunction "RF_SW_CTRL_5_2") (pintype "passive"))
    )
    (net (code "72") (name "unconnected-(MOD1-USB2_AVDD33-Pad28)") (class "Default")
      (node (ref "MOD1") (pin "28") (pinfunction "USB2_AVDD33_28") (pintype "passive"))
    )
    (net (code "73") (name "unconnected-(MOD1-USB2_DM-Pad24)") (class "Default")
      (node (ref "MOD1") (pin "24") (pinfunction "USB2_DM_24") (pintype "passive"))
    )
    (net (code "74") (name "unconnected-(MOD1-USB2_DP-Pad25)") (class "Default")
      (node (ref "MOD1") (pin "25") (pinfunction "USB2_DP_25") (pintype "passive"))
    )
    (net (code "75") (name "unconnected-(MOD1-USB2_RREF-Pad26)") (class "Default")
      (node (ref "MOD1") (pin "26") (pinfunction "USB2_RREF_26") (pintype "passive"))
    )
    (net (code "76") (name "unconnected-(U7-LOAD-PadB1)") (class "Default")
      (node (ref "U7") (pin "B1") (pinfunction "LOAD_B1") (pintype "passive"))
    )
    (net (code "77") (name "unconnected-(U16-XTB-Pad4)") (class "Default")
      (node (ref "U16") (pin "4") (pinfunction "XTB_4") (pintype "passive"))
    )
  )
)
